# cheetah_driver_integrated_v2.net
KiCad netlist of a schematic drawn in EAGLE
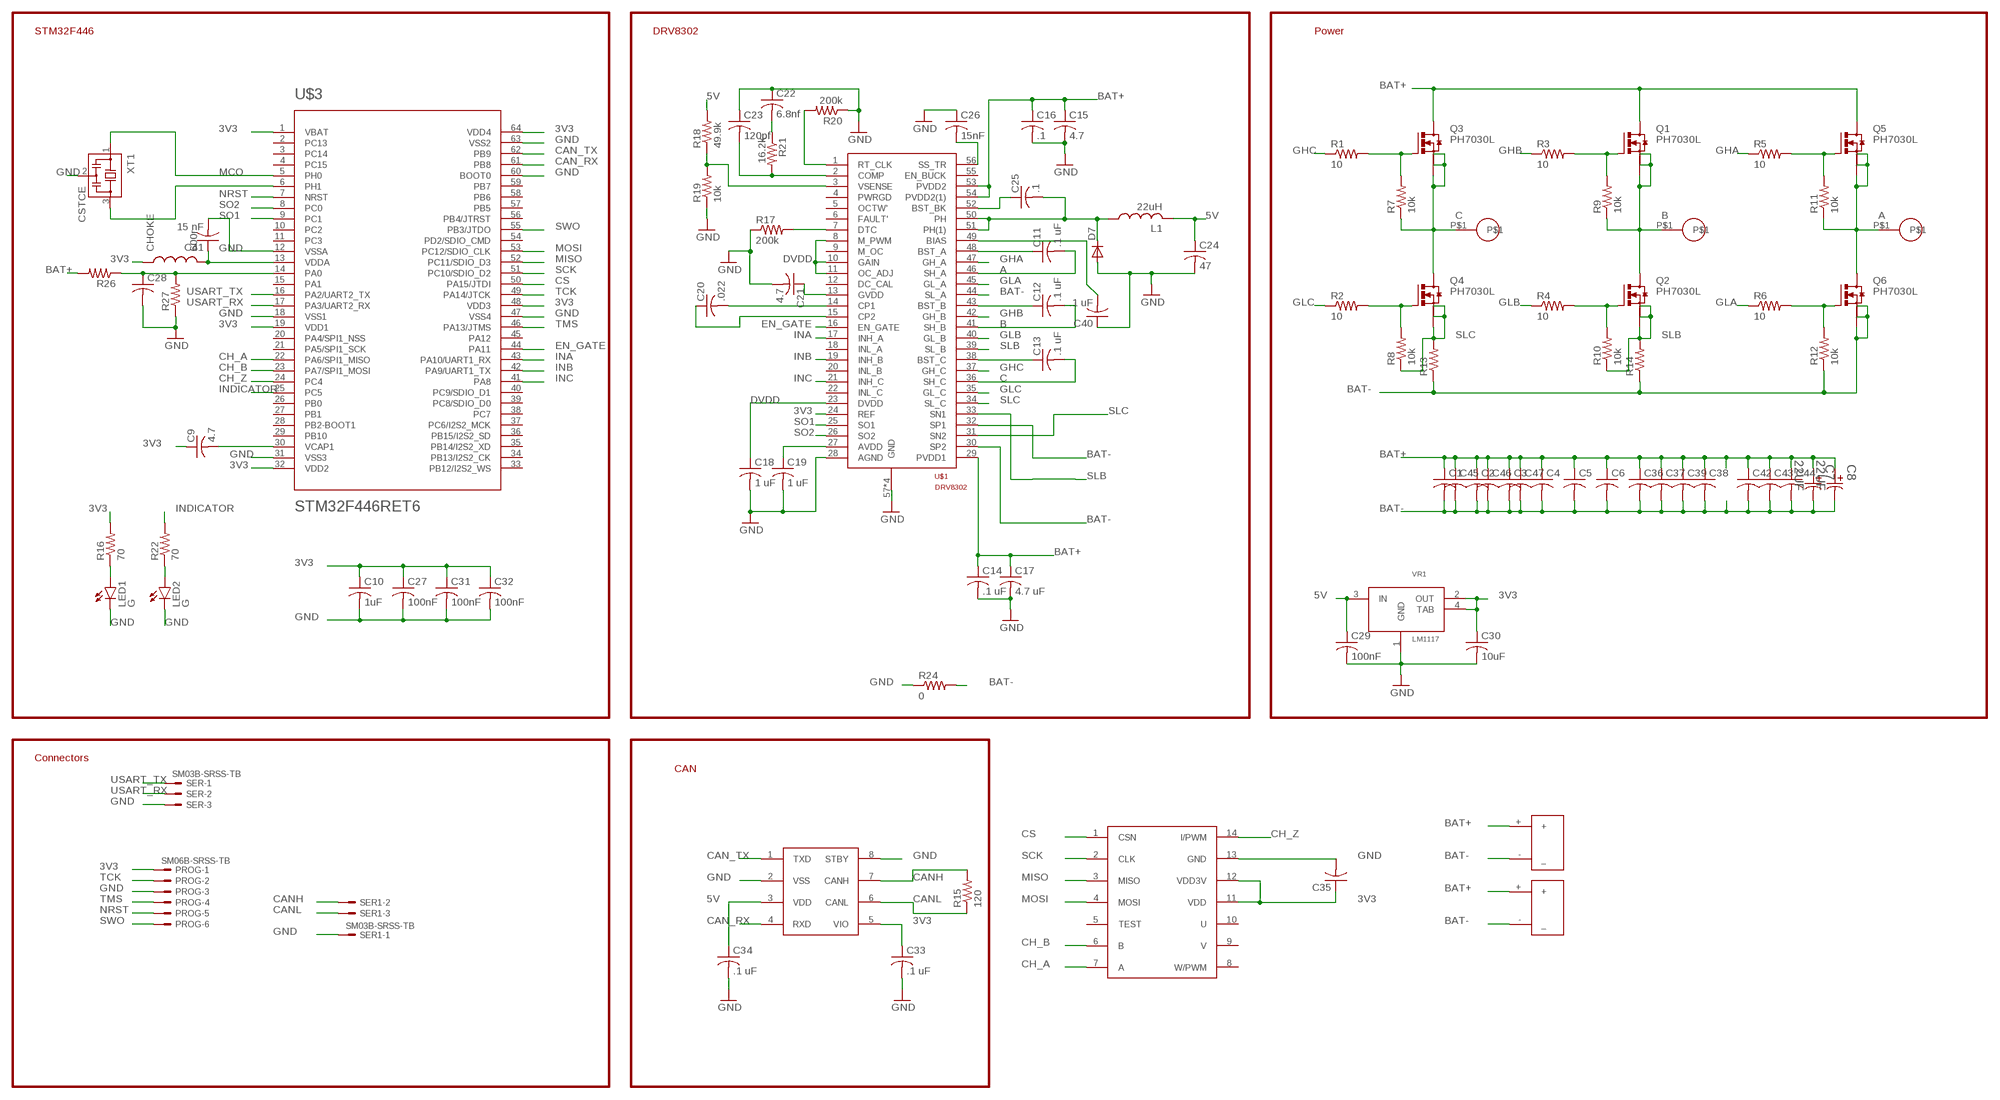
[diagram p0: schematic, sheet 1]

(export (version "E")
  (design (tool "Eeschema 10.0.6"))
  (components
    (comp (ref "C1")
      (value "C-USC1206")
      (footprint "eagle-import:C1206")
      (libsource (lib "eagle-import") (part "C-USC1206"))
    )
    (comp (ref "C2")
      (value "C-USC1206")
      (footprint "eagle-import:C1206")
      (libsource (lib "eagle-import") (part "C-USC1206"))
    )
    (comp (ref "C3")
      (value "C-USC1206")
      (footprint "eagle-import:C1206")
      (libsource (lib "eagle-import") (part "C-USC1206"))
    )
    (comp (ref "C4")
      (value "C-USC1206")
      (footprint "eagle-import:C1206")
      (libsource (lib "eagle-import") (part "C-USC1206"))
    )
    (comp (ref "C5")
      (value "C-USC1206")
      (footprint "eagle-import:C1206")
      (libsource (lib "eagle-import") (part "C-USC1206"))
    )
    (comp (ref "C6")
      (value "C-USC1206")
      (footprint "eagle-import:C1206")
      (libsource (lib "eagle-import") (part "C-USC1206"))
    )
    (comp (ref "C7")
      (value "22UF")
      (footprint "eagle-import:CAPAE660X610N")
      (fields (field (name "MPN") "EEE-HD1V220AP") (field (name "TOLERANCE") "±20 %"))
      (libsource (lib "eagle-import") (part "EEE--CASE-DHD1V220AP"))
    )
    (comp (ref "C8")
      (value "22UF")
      (footprint "eagle-import:CAPAE660X610N")
      (fields (field (name "MPN") "EEE-HD1V220AP") (field (name "TOLERANCE") "±20 %"))
      (libsource (lib "eagle-import") (part "EEE--CASE-DHD1V220AP"))
    )
    (comp (ref "C9")
      (value "4.7")
      (footprint "eagle-import:C0603")
      (libsource (lib "eagle-import") (part "C-USC0603"))
    )
    (comp (ref "C10")
      (value "1uF")
      (footprint "eagle-import:C0603")
      (libsource (lib "eagle-import") (part "C-USC0603"))
    )
    (comp (ref "C11")
      (value ".1 uF")
      (footprint "eagle-import:C0603")
      (libsource (lib "eagle-import") (part "C-USC0603"))
    )
    (comp (ref "C12")
      (value ".1 uF")
      (footprint "eagle-import:C0603")
      (libsource (lib "eagle-import") (part "C-USC0603"))
    )
    (comp (ref "C13")
      (value ".1 uF")
      (footprint "eagle-import:C0603")
      (libsource (lib "eagle-import") (part "C-USC0603"))
    )
    (comp (ref "C14")
      (value ".1 uF")
      (footprint "eagle-import:C0603")
      (libsource (lib "eagle-import") (part "C-USC0603"))
    )
    (comp (ref "C15")
      (value "4.7")
      (footprint "eagle-import:C0805")
      (libsource (lib "eagle-import") (part "C-USC0805"))
    )
    (comp (ref "C16")
      (value ".1")
      (footprint "eagle-import:C0603")
      (libsource (lib "eagle-import") (part "C-USC0603"))
    )
    (comp (ref "C17")
      (value "4.7 uF")
      (footprint "eagle-import:C0805")
      (libsource (lib "eagle-import") (part "C-USC0805"))
    )
    (comp (ref "C18")
      (value "1 uF")
      (footprint "eagle-import:C0603")
      (libsource (lib "eagle-import") (part "C-USC0603"))
    )
    (comp (ref "C19")
      (value "1 uF")
      (footprint "eagle-import:C0603")
      (libsource (lib "eagle-import") (part "C-USC0603"))
    )
    (comp (ref "C20")
      (value ".022")
      (footprint "eagle-import:C0603")
      (libsource (lib "eagle-import") (part "C-USC0603"))
    )
    (comp (ref "C21")
      (value "4.7")
      (footprint "eagle-import:C0805")
      (libsource (lib "eagle-import") (part "C-USC0805"))
    )
    (comp (ref "C22")
      (value "6.8nf")
      (footprint "eagle-import:C0603")
      (libsource (lib "eagle-import") (part "C-USC0603"))
    )
    (comp (ref "C23")
      (value "120pf")
      (footprint "eagle-import:C0603")
      (libsource (lib "eagle-import") (part "C-USC0603"))
    )
    (comp (ref "C24")
      (value "47")
      (footprint "eagle-import:C1210")
      (libsource (lib "eagle-import") (part "C-USC1210"))
    )
    (comp (ref "C25")
      (value ".1")
      (footprint "eagle-import:C0603")
      (libsource (lib "eagle-import") (part "C-USC0603"))
    )
    (comp (ref "C26")
      (value "15nF")
      (footprint "eagle-import:C0603")
      (libsource (lib "eagle-import") (part "C-USC0603"))
    )
    (comp (ref "C27")
      (value "100nF")
      (footprint "eagle-import:C0603")
      (libsource (lib "eagle-import") (part "C-USC0603"))
    )
    (comp (ref "C28")
      (value "C-USC0603")
      (footprint "eagle-import:C0603")
      (libsource (lib "eagle-import") (part "C-USC0603"))
    )
    (comp (ref "C29")
      (value "100nF")
      (footprint "eagle-import:C0603")
      (libsource (lib "eagle-import") (part "C-USC0603"))
    )
    (comp (ref "C30")
      (value "10uF")
      (footprint "eagle-import:C0805K")
      (libsource (lib "eagle-import") (part "C-USC0805K"))
    )
    (comp (ref "C31")
      (value "100nF")
      (footprint "eagle-import:C0603")
      (libsource (lib "eagle-import") (part "C-USC0603"))
    )
    (comp (ref "C32")
      (value "100nF")
      (footprint "eagle-import:C0603")
      (libsource (lib "eagle-import") (part "C-USC0603"))
    )
    (comp (ref "C33")
      (value ".1 uF")
      (footprint "eagle-import:C0603K")
      (libsource (lib "eagle-import") (part "C-USC0603K"))
    )
    (comp (ref "C34")
      (value ".1 uF")
      (footprint "eagle-import:C0603K")
      (libsource (lib "eagle-import") (part "C-USC0603K"))
    )
    (comp (ref "C35")
      (value "C-USC0603")
      (footprint "eagle-import:C0603")
      (libsource (lib "eagle-import") (part "C-USC0603"))
    )
    (comp (ref "C36")
      (value "C-USC1206")
      (footprint "eagle-import:C1206")
      (libsource (lib "eagle-import") (part "C-USC1206"))
    )
    (comp (ref "C37")
      (value "C-USC1206")
      (footprint "eagle-import:C1206")
      (libsource (lib "eagle-import") (part "C-USC1206"))
    )
    (comp (ref "C38")
      (value "C-USC1206")
      (footprint "eagle-import:C1206")
      (libsource (lib "eagle-import") (part "C-USC1206"))
    )
    (comp (ref "C39")
      (value "C-USC1206")
      (footprint "eagle-import:C1206")
      (libsource (lib "eagle-import") (part "C-USC1206"))
    )
    (comp (ref "C40")
      (value ".1 uF")
      (footprint "eagle-import:C0603")
      (libsource (lib "eagle-import") (part "C-USC0603"))
    )
    (comp (ref "C41")
      (value "15 nF")
      (footprint "eagle-import:C0603")
      (libsource (lib "eagle-import") (part "C-USC0603"))
    )
    (comp (ref "C42")
      (value "C-USC1206")
      (footprint "eagle-import:C1206")
      (libsource (lib "eagle-import") (part "C-USC1206"))
    )
    (comp (ref "C43")
      (value "C-USC1206")
      (footprint "eagle-import:C1206")
      (libsource (lib "eagle-import") (part "C-USC1206"))
    )
    (comp (ref "C44")
      (value "C-USC1206")
      (footprint "eagle-import:C1206")
      (libsource (lib "eagle-import") (part "C-USC1206"))
    )
    (comp (ref "C45")
      (value "C-USC1206")
      (footprint "eagle-import:C1206")
      (libsource (lib "eagle-import") (part "C-USC1206"))
    )
    (comp (ref "C46")
      (value "C-USC1206")
      (footprint "eagle-import:C1206")
      (libsource (lib "eagle-import") (part "C-USC1206"))
    )
    (comp (ref "C47")
      (value "C-USC1206")
      (footprint "eagle-import:C1206")
      (libsource (lib "eagle-import") (part "C-USC1206"))
    )
    (comp (ref "CHOKE")
      (value "600r")
      (footprint "eagle-import:0603")
      (libsource (lib "eagle-import") (part "INDUCTOR0603"))
    )
    (comp (ref "D7")
      (value "DIODE-DO-214AC")
      (footprint "eagle-import:DO-214AC")
      (libsource (lib "eagle-import") (part "DIODE-DO-214AC"))
    )
    (comp (ref "L1")
      (value "22uH")
      (footprint "eagle-import:L4532P")
      (libsource (lib "eagle-import") (part "L-USL4532P"))
    )
    (comp (ref "LED1")
      (value "G")
      (footprint "eagle-import:LED-0603")
      (libsource (lib "eagle-import") (part "LED0603"))
    )
    (comp (ref "LED2")
      (value "G")
      (footprint "eagle-import:LED-0603")
      (libsource (lib "eagle-import") (part "LED0603"))
    )
    (comp (ref "PROG")
      (value "SM06B-SRSS-TB")
      (footprint "eagle-import:SM06B-SRSS-TB")
      (libsource (lib "eagle-import") (part "?M06B-SRSS-TBS"))
    )
    (comp (ref "Q1")
      (value "PH7030L")
      (footprint "eagle-import:SOT669")
      (libsource (lib "eagle-import") (part "PH7030L"))
    )
    (comp (ref "Q2")
      (value "PH7030L")
      (footprint "eagle-import:SOT669")
      (libsource (lib "eagle-import") (part "PH7030L"))
    )
    (comp (ref "Q3")
      (value "PH7030L")
      (footprint "eagle-import:SOT669")
      (libsource (lib "eagle-import") (part "PH7030L"))
    )
    (comp (ref "Q4")
      (value "PH7030L")
      (footprint "eagle-import:SOT669")
      (libsource (lib "eagle-import") (part "PH7030L"))
    )
    (comp (ref "Q5")
      (value "PH7030L")
      (footprint "eagle-import:SOT669")
      (libsource (lib "eagle-import") (part "PH7030L"))
    )
    (comp (ref "Q6")
      (value "PH7030L")
      (footprint "eagle-import:SOT669")
      (libsource (lib "eagle-import") (part "PH7030L"))
    )
    (comp (ref "R1")
      (value "10")
      (footprint "eagle-import:R0603")
      (libsource (lib "eagle-import") (part "R-US_R0603"))
    )
    (comp (ref "R2")
      (value "10")
      (footprint "eagle-import:R0603")
      (libsource (lib "eagle-import") (part "R-US_R0603"))
    )
    (comp (ref "R3")
      (value "10")
      (footprint "eagle-import:R0603")
      (libsource (lib "eagle-import") (part "R-US_R0603"))
    )
    (comp (ref "R4")
      (value "10")
      (footprint "eagle-import:R0603")
      (libsource (lib "eagle-import") (part "R-US_R0603"))
    )
    (comp (ref "R5")
      (value "10")
      (footprint "eagle-import:R0603")
      (libsource (lib "eagle-import") (part "R-US_R0603"))
    )
    (comp (ref "R6")
      (value "10")
      (footprint "eagle-import:R0603")
      (libsource (lib "eagle-import") (part "R-US_R0603"))
    )
    (comp (ref "R7")
      (value "10k")
      (footprint "eagle-import:R0603")
      (libsource (lib "eagle-import") (part "R-US_R0603"))
    )
    (comp (ref "R8")
      (value "10k")
      (footprint "eagle-import:R0603")
      (libsource (lib "eagle-import") (part "R-US_R0603"))
    )
    (comp (ref "R9")
      (value "10k")
      (footprint "eagle-import:R0603")
      (libsource (lib "eagle-import") (part "R-US_R0603"))
    )
    (comp (ref "R10")
      (value "10k")
      (footprint "eagle-import:R0603")
      (libsource (lib "eagle-import") (part "R-US_R0603"))
    )
    (comp (ref "R11")
      (value "10k")
      (footprint "eagle-import:R0603")
      (libsource (lib "eagle-import") (part "R-US_R0603"))
    )
    (comp (ref "R12")
      (value "10k")
      (footprint "eagle-import:R0603")
      (libsource (lib "eagle-import") (part "R-US_R0603"))
    )
    (comp (ref "R13")
      (value "R-US_R1210")
      (footprint "eagle-import:R1210")
      (libsource (lib "eagle-import") (part "R-US_R1210"))
    )
    (comp (ref "R14")
      (value "R-US_R1210")
      (footprint "eagle-import:R1210")
      (libsource (lib "eagle-import") (part "R-US_R1210"))
    )
    (comp (ref "R15")
      (value "120")
      (footprint "eagle-import:R0603")
      (libsource (lib "eagle-import") (part "R-US_R0603"))
    )
    (comp (ref "R16")
      (value "70")
      (footprint "eagle-import:R0603")
      (libsource (lib "eagle-import") (part "R-US_R0603"))
    )
    (comp (ref "R17")
      (value "200k")
      (footprint "eagle-import:R0603")
      (libsource (lib "eagle-import") (part "R-US_R0603"))
    )
    (comp (ref "R18")
      (value "49.9k")
      (footprint "eagle-import:R0603")
      (libsource (lib "eagle-import") (part "R-US_R0603"))
    )
    (comp (ref "R19")
      (value "10k")
      (footprint "eagle-import:R0603")
      (libsource (lib "eagle-import") (part "R-US_R0603"))
    )
    (comp (ref "R20")
      (value "200k")
      (footprint "eagle-import:R0603")
      (libsource (lib "eagle-import") (part "R-US_R0603"))
    )
    (comp (ref "R21")
      (value "16.2k")
      (footprint "eagle-import:R0603")
      (libsource (lib "eagle-import") (part "R-US_R0603"))
    )
    (comp (ref "R22")
      (value "70")
      (footprint "eagle-import:R0603")
      (libsource (lib "eagle-import") (part "R-US_R0603"))
    )
    (comp (ref "R24")
      (value "0")
      (footprint "eagle-import:R0603")
      (libsource (lib "eagle-import") (part "R-US_R0603"))
    )
    (comp (ref "R26")
      (value "R-US_R0603")
      (footprint "eagle-import:R0603")
      (libsource (lib "eagle-import") (part "R-US_R0603"))
    )
    (comp (ref "R27")
      (value "R-US_R0603")
      (footprint "eagle-import:R0603")
      (libsource (lib "eagle-import") (part "R-US_R0603"))
    )
    (comp (ref "SER")
      (value "SM03B-SRSS-TB")
      (footprint "eagle-import:SM03B-SRSS-TB")
      (libsource (lib "eagle-import") (part "?M03B-SRSS-TBS"))
    )
    (comp (ref "SER1")
      (value "SM03B-SRSS-TB")
      (footprint "eagle-import:SM03B-SRSS-TB")
      (libsource (lib "eagle-import") (part "?M03B-SRSS-TBS"))
    )
    (comp (ref "U$1")
      (value "DRV8302")
      (footprint "eagle-import:HTSSOP56")
      (libsource (lib "eagle-import") (part "DRV8302"))
    )
    (comp (ref "U$2")
      (value "18_AWG_PAD")
      (footprint "eagle-import:18_AWG_PAD")
      (libsource (lib "eagle-import") (part "18_AWG_PAD"))
    )
    (comp (ref "U$3")
      (value "STM32F446RET6")
      (footprint "eagle-import:TQFP64")
      (libsource (lib "eagle-import") (part "STM32F446RET6"))
    )
    (comp (ref "U$4")
      (value "18_AWG_PAD")
      (footprint "eagle-import:18_AWG_PAD")
      (libsource (lib "eagle-import") (part "18_AWG_PAD"))
    )
    (comp (ref "U$5")
      (value "18_AWG_PAD")
      (footprint "eagle-import:18_AWG_PAD")
      (libsource (lib "eagle-import") (part "18_AWG_PAD"))
    )
    (comp (ref "U$6")
      (value "MCP2561")
      (footprint "eagle-import:SO08")
      (libsource (lib "eagle-import") (part "MCP2561"))
    )
    (comp (ref "U$7")
      (value "AS5147P")
      (footprint "eagle-import:TSSOP14")
      (libsource (lib "eagle-import") (part "AS5147P"))
    )
    (comp (ref "U$8")
      (value "DC_CONNECTOR")
      (footprint "eagle-import:XT30_HORIZONTAL")
      (libsource (lib "eagle-import") (part "DC_CONNECTOR"))
    )
    (comp (ref "U$9")
      (value "DC_CONNECTOR")
      (footprint "eagle-import:XT30_HORIZONTAL")
      (libsource (lib "eagle-import") (part "DC_CONNECTOR"))
    )
    (comp (ref "VR1")
      (value "LM1117")
      (footprint "eagle-import:SOT-223")
      (libsource (lib "eagle-import") (part "LM1117"))
    )
    (comp (ref "XT1")
      (value "CSTCE")
      (footprint "eagle-import:CSTCE")
      (libsource (lib "eagle-import") (part "CSTCE"))
    )
  )
  (nets
    (net (code "1") (name "/3V3") (class "Default")
      (node (ref "C10") (pin "1") (pinfunction "1_1") (pintype "passive"))
      (node (ref "C27") (pin "1") (pinfunction "1_1") (pintype "passive"))
      (node (ref "C30") (pin "1") (pinfunction "1_1") (pintype "passive"))
      (node (ref "C31") (pin "1") (pinfunction "1_1") (pintype "passive"))
      (node (ref "C32") (pin "1") (pinfunction "1_1") (pintype "passive"))
      (node (ref "C33") (pin "1") (pinfunction "1_1") (pintype "passive"))
      (node (ref "C35") (pin "1") (pinfunction "1_1") (pintype "passive"))
      (node (ref "C9") (pin "1") (pinfunction "1_1") (pintype "passive"))
      (node (ref "CHOKE") (pin "1") (pinfunction "1_1") (pintype "passive"))
      (node (ref "PROG") (pin "1") (pinfunction "S_1") (pintype "passive"))
      (node (ref "R16") (pin "2") (pinfunction "2_2") (pintype "passive"))
      (node (ref "U$1") (pin "24") (pinfunction "REF_24") (pintype "bidirectional"))
      (node (ref "U$3") (pin "1") (pinfunction "VBAT_1") (pintype "bidirectional"))
      (node (ref "U$3") (pin "19") (pinfunction "VDD1_19") (pintype "bidirectional"))
      (node (ref "U$3") (pin "32") (pinfunction "VDD2_32") (pintype "bidirectional"))
      (node (ref "U$3") (pin "48") (pinfunction "VDD3_48") (pintype "bidirectional"))
      (node (ref "U$3") (pin "64") (pinfunction "VDD4_64") (pintype "bidirectional"))
      (node (ref "U$6") (pin "5") (pinfunction "VIO_5") (pintype "bidirectional"))
      (node (ref "U$7") (pin "11") (pinfunction "VDD_11") (pintype "bidirectional"))
      (node (ref "U$7") (pin "12") (pinfunction "VDD3V_12") (pintype "bidirectional"))
      (node (ref "VR1") (pin "2") (pinfunction "OUT_2") (pintype "bidirectional"))
      (node (ref "VR1") (pin "4") (pinfunction "TAB_4") (pintype "bidirectional"))
    )
    (net (code "2") (name "/5V") (class "Default")
      (node (ref "C24") (pin "1") (pinfunction "1_1") (pintype "passive"))
      (node (ref "C29") (pin "1") (pinfunction "1_1") (pintype "passive"))
      (node (ref "C34") (pin "1") (pinfunction "1_1") (pintype "passive"))
      (node (ref "L1") (pin "2") (pinfunction "2_2") (pintype "passive"))
      (node (ref "R18") (pin "2") (pinfunction "2_2") (pintype "passive"))
      (node (ref "U$6") (pin "3") (pinfunction "VDD_3") (pintype "bidirectional"))
      (node (ref "VR1") (pin "3") (pinfunction "IN_3") (pintype "bidirectional"))
    )
    (net (code "3") (name "/A") (class "Default")
      (node (ref "C11") (pin "2") (pinfunction "2_2") (pintype "passive"))
      (node (ref "Q5") (pin "1") (pinfunction "S_1") (pintype "passive"))
      (node (ref "Q5") (pin "2") (pinfunction "S_2") (pintype "passive"))
      (node (ref "Q5") (pin "3") (pinfunction "S_3") (pintype "passive"))
      (node (ref "Q6") (pin "MB") (pinfunction "D_MB") (pintype "passive"))
      (node (ref "R11") (pin "1") (pinfunction "1_1") (pintype "passive"))
      (node (ref "U$1") (pin "46") (pinfunction "SH_A_46") (pintype "bidirectional"))
      (node (ref "U$5") (pin "P$1") (pinfunction "P$1_P$1") (pintype "bidirectional"))
    )
    (net (code "4") (name "/B") (class "Default")
      (node (ref "C12") (pin "2") (pinfunction "2_2") (pintype "passive"))
      (node (ref "Q1") (pin "1") (pinfunction "S_1") (pintype "passive"))
      (node (ref "Q1") (pin "2") (pinfunction "S_2") (pintype "passive"))
      (node (ref "Q1") (pin "3") (pinfunction "S_3") (pintype "passive"))
      (node (ref "Q2") (pin "MB") (pinfunction "D_MB") (pintype "passive"))
      (node (ref "R9") (pin "1") (pinfunction "1_1") (pintype "passive"))
      (node (ref "U$1") (pin "41") (pinfunction "SH_B_41") (pintype "bidirectional"))
      (node (ref "U$4") (pin "P$1") (pinfunction "P$1_P$1") (pintype "bidirectional"))
    )
    (net (code "5") (name "/BAT+") (class "Default")
      (node (ref "C1") (pin "1") (pinfunction "1_1") (pintype "passive"))
      (node (ref "C14") (pin "1") (pinfunction "1_1") (pintype "passive"))
      (node (ref "C15") (pin "1") (pinfunction "1_1") (pintype "passive"))
      (node (ref "C16") (pin "1") (pinfunction "1_1") (pintype "passive"))
      (node (ref "C17") (pin "1") (pinfunction "1_1") (pintype "passive"))
      (node (ref "C2") (pin "1") (pinfunction "1_1") (pintype "passive"))
      (node (ref "C3") (pin "1") (pinfunction "1_1") (pintype "passive"))
      (node (ref "C36") (pin "1") (pinfunction "1_1") (pintype "passive"))
      (node (ref "C37") (pin "1") (pinfunction "1_1") (pintype "passive"))
      (node (ref "C38") (pin "1") (pinfunction "1_1") (pintype "passive"))
      (node (ref "C39") (pin "1") (pinfunction "1_1") (pintype "passive"))
      (node (ref "C4") (pin "1") (pinfunction "1_1") (pintype "passive"))
      (node (ref "C42") (pin "1") (pinfunction "1_1") (pintype "passive"))
      (node (ref "C43") (pin "1") (pinfunction "1_1") (pintype "passive"))
      (node (ref "C44") (pin "1") (pinfunction "1_1") (pintype "passive"))
      (node (ref "C45") (pin "1") (pinfunction "1_1") (pintype "passive"))
      (node (ref "C46") (pin "1") (pinfunction "1_1") (pintype "passive"))
      (node (ref "C47") (pin "1") (pinfunction "1_1") (pintype "passive"))
      (node (ref "C5") (pin "1") (pinfunction "1_1") (pintype "passive"))
      (node (ref "C6") (pin "1") (pinfunction "1_1") (pintype "passive"))
      (node (ref "C7") (pin "1") (pinfunction "1_1") (pintype "passive"))
      (node (ref "C8") (pin "1") (pinfunction "1_1") (pintype "passive"))
      (node (ref "Q1") (pin "MB") (pinfunction "D_MB") (pintype "passive"))
      (node (ref "Q3") (pin "MB") (pinfunction "D_MB") (pintype "passive"))
      (node (ref "Q5") (pin "MB") (pinfunction "D_MB") (pintype "passive"))
      (node (ref "R26") (pin "2") (pinfunction "2_2") (pintype "passive"))
      (node (ref "U$1") (pin "29") (pinfunction "PVDD1_29") (pintype "bidirectional"))
      (node (ref "U$1") (pin "53") (pinfunction "PVDD2_53") (pintype "bidirectional"))
      (node (ref "U$1") (pin "54") (pinfunction "PVDD2(1)_54") (pintype "bidirectional"))
      (node (ref "U$8") (pin "+") (pinfunction "+_+") (pintype "bidirectional"))
      (node (ref "U$9") (pin "+") (pinfunction "+_+") (pintype "bidirectional"))
    )
    (net (code "6") (name "/BAT-") (class "Default")
      (node (ref "C1") (pin "2") (pinfunction "2_2") (pintype "passive"))
      (node (ref "C2") (pin "2") (pinfunction "2_2") (pintype "passive"))
      (node (ref "C3") (pin "2") (pinfunction "2_2") (pintype "passive"))
      (node (ref "C36") (pin "2") (pinfunction "2_2") (pintype "passive"))
      (node (ref "C37") (pin "2") (pinfunction "2_2") (pintype "passive"))
      (node (ref "C38") (pin "2") (pinfunction "2_2") (pintype "passive"))
      (node (ref "C39") (pin "2") (pinfunction "2_2") (pintype "passive"))
      (node (ref "C4") (pin "2") (pinfunction "2_2") (pintype "passive"))
      (node (ref "C42") (pin "2") (pinfunction "2_2") (pintype "passive"))
      (node (ref "C43") (pin "2") (pinfunction "2_2") (pintype "passive"))
      (node (ref "C44") (pin "2") (pinfunction "2_2") (pintype "passive"))
      (node (ref "C45") (pin "2") (pinfunction "2_2") (pintype "passive"))
      (node (ref "C46") (pin "2") (pinfunction "2_2") (pintype "passive"))
      (node (ref "C47") (pin "2") (pinfunction "2_2") (pintype "passive"))
      (node (ref "C5") (pin "2") (pinfunction "2_2") (pintype "passive"))
      (node (ref "C6") (pin "2") (pinfunction "2_2") (pintype "passive"))
      (node (ref "C7") (pin "2") (pinfunction "2_2") (pintype "passive"))
      (node (ref "C8") (pin "2") (pinfunction "2_2") (pintype "passive"))
      (node (ref "Q6") (pin "1") (pinfunction "S_1") (pintype "passive"))
      (node (ref "Q6") (pin "2") (pinfunction "S_2") (pintype "passive"))
      (node (ref "Q6") (pin "3") (pinfunction "S_3") (pintype "passive"))
      (node (ref "R12") (pin "1") (pinfunction "1_1") (pintype "passive"))
      (node (ref "R13") (pin "1") (pinfunction "1_1") (pintype "passive"))
      (node (ref "R14") (pin "1") (pinfunction "1_1") (pintype "passive"))
      (node (ref "R24") (pin "2") (pinfunction "2_2") (pintype "passive"))
      (node (ref "U$1") (pin "30") (pinfunction "SP2_30") (pintype "bidirectional"))
      (node (ref "U$1") (pin "32") (pinfunction "SP1_32") (pintype "bidirectional"))
      (node (ref "U$1") (pin "44") (pinfunction "SL_A_44") (pintype "bidirectional"))
      (node (ref "U$8") (pin "-") (pinfunction "__-") (pintype "bidirectional"))
      (node (ref "U$9") (pin "-") (pinfunction "__-") (pintype "bidirectional"))
    )
    (net (code "7") (name "/C") (class "Default")
      (node (ref "C13") (pin "2") (pinfunction "2_2") (pintype "passive"))
      (node (ref "Q3") (pin "1") (pinfunction "S_1") (pintype "passive"))
      (node (ref "Q3") (pin "2") (pinfunction "S_2") (pintype "passive"))
      (node (ref "Q3") (pin "3") (pinfunction "S_3") (pintype "passive"))
      (node (ref "Q4") (pin "MB") (pinfunction "D_MB") (pintype "passive"))
      (node (ref "R7") (pin "1") (pinfunction "1_1") (pintype "passive"))
      (node (ref "U$1") (pin "36") (pinfunction "SH_C_36") (pintype "bidirectional"))
      (node (ref "U$2") (pin "P$1") (pinfunction "P$1_P$1") (pintype "bidirectional"))
    )
    (net (code "8") (name "/CANH") (class "Default")
      (node (ref "R15") (pin "2") (pinfunction "2_2") (pintype "passive"))
      (node (ref "SER1") (pin "2") (pinfunction "S_2") (pintype "passive"))
      (node (ref "U$6") (pin "7") (pinfunction "CANH_7") (pintype "bidirectional"))
    )
    (net (code "9") (name "/CANL") (class "Default")
      (node (ref "R15") (pin "1") (pinfunction "1_1") (pintype "passive"))
      (node (ref "SER1") (pin "3") (pinfunction "S_3") (pintype "passive"))
      (node (ref "U$6") (pin "6") (pinfunction "CANL_6") (pintype "bidirectional"))
    )
    (net (code "10") (name "/CAN_RX") (class "Default")
      (node (ref "U$3") (pin "61") (pinfunction "PB8_61") (pintype "bidirectional"))
      (node (ref "U$6") (pin "4") (pinfunction "RXD_4") (pintype "bidirectional"))
    )
    (net (code "11") (name "/CAN_TX") (class "Default")
      (node (ref "U$3") (pin "62") (pinfunction "PB9_62") (pintype "bidirectional"))
      (node (ref "U$6") (pin "1") (pinfunction "TXD_1") (pintype "bidirectional"))
    )
    (net (code "12") (name "/CH_A") (class "Default")
      (node (ref "U$3") (pin "22") (pinfunction "PA6/SPI1_MISO_22") (pintype "bidirectional"))
      (node (ref "U$7") (pin "7") (pinfunction "A_7") (pintype "bidirectional"))
    )
    (net (code "13") (name "/CH_B") (class "Default")
      (node (ref "U$3") (pin "23") (pinfunction "PA7/SPI1_MOSI_23") (pintype "bidirectional"))
      (node (ref "U$7") (pin "6") (pinfunction "B_6") (pintype "bidirectional"))
    )
    (net (code "14") (name "/CH_Z") (class "Default")
      (node (ref "U$3") (pin "24") (pinfunction "PC4_24") (pintype "bidirectional"))
      (node (ref "U$7") (pin "14") (pinfunction "I/PWM_14") (pintype "bidirectional"))
    )
    (net (code "15") (name "/CS") (class "Default")
      (node (ref "U$3") (pin "50") (pinfunction "PA15/JTDI_50") (pintype "bidirectional"))
      (node (ref "U$7") (pin "1") (pinfunction "CSN_1") (pintype "bidirectional"))
    )
    (net (code "16") (name "/DVDD") (class "Default")
      (node (ref "C18") (pin "1") (pinfunction "1_1") (pintype "passive"))
      (node (ref "U$1") (pin "10") (pinfunction "GAIN_10") (pintype "bidirectional"))
      (node (ref "U$1") (pin "11") (pinfunction "OC_ADJ_11") (pintype "bidirectional"))
      (node (ref "U$1") (pin "23") (pinfunction "DVDD_23") (pintype "bidirectional"))
      (node (ref "U$1") (pin "8") (pinfunction "M_PWM_8") (pintype "bidirectional"))
    )
    (net (code "17") (name "/EN_GATE") (class "Default")
      (node (ref "U$1") (pin "16") (pinfunction "EN_GATE_16") (pintype "bidirectional"))
      (node (ref "U$3") (pin "44") (pinfunction "PA11_44") (pintype "bidirectional"))
    )
    (net (code "18") (name "/GHA") (class "Default")
      (node (ref "R5") (pin "1") (pinfunction "1_1") (pintype "passive"))
      (node (ref "U$1") (pin "47") (pinfunction "GH_A_47") (pintype "bidirectional"))
    )
    (net (code "19") (name "/GHB") (class "Default")
      (node (ref "R3") (pin "1") (pinfunction "1_1") (pintype "passive"))
      (node (ref "U$1") (pin "42") (pinfunction "GH_B_42") (pintype "bidirectional"))
    )
    (net (code "20") (name "/GHC") (class "Default")
      (node (ref "R1") (pin "1") (pinfunction "1_1") (pintype "passive"))
      (node (ref "U$1") (pin "37") (pinfunction "GH_C_37") (pintype "bidirectional"))
    )
    (net (code "21") (name "/GLA") (class "Default")
      (node (ref "R6") (pin "1") (pinfunction "1_1") (pintype "passive"))
      (node (ref "U$1") (pin "45") (pinfunction "GL_A_45") (pintype "bidirectional"))
    )
    (net (code "22") (name "/GLB") (class "Default")
      (node (ref "R4") (pin "1") (pinfunction "1_1") (pintype "passive"))
      (node (ref "U$1") (pin "40") (pinfunction "GL_B_40") (pintype "bidirectional"))
    )
    (net (code "23") (name "/GLC") (class "Default")
      (node (ref "R2") (pin "1") (pinfunction "1_1") (pintype "passive"))
      (node (ref "U$1") (pin "35") (pinfunction "GL_C_35") (pintype "bidirectional"))
    )
    (net (code "24") (name "/INA") (class "Default")
      (node (ref "U$1") (pin "17") (pinfunction "INH_A_17") (pintype "bidirectional"))
      (node (ref "U$3") (pin "43") (pinfunction "PA10/UART1_RX_43") (pintype "bidirectional"))
    )
    (net (code "25") (name "/INB") (class "Default")
      (node (ref "U$1") (pin "19") (pinfunction "INH_B_19") (pintype "bidirectional"))
      (node (ref "U$3") (pin "42") (pinfunction "PA9/UART1_TX_42") (pintype "bidirectional"))
    )
    (net (code "26") (name "/INC") (class "Default")
      (node (ref "U$1") (pin "21") (pinfunction "INH_C_21") (pintype "bidirectional"))
      (node (ref "U$3") (pin "41") (pinfunction "PA8_41") (pintype "bidirectional"))
    )
    (net (code "27") (name "/INDICATOR") (class "Default")
      (node (ref "R22") (pin "2") (pinfunction "2_2") (pintype "passive"))
      (node (ref "U$3") (pin "25") (pinfunction "PC5_25") (pintype "bidirectional"))
    )
    (net (code "28") (name "/MCO") (class "Default")
      (node (ref "U$3") (pin "5") (pinfunction "PH0_5") (pintype "bidirectional"))
      (node (ref "XT1") (pin "1") (pinfunction "1_1") (pintype "passive"))
    )
    (net (code "29") (name "/MISO") (class "Default")
      (node (ref "U$3") (pin "52") (pinfunction "PC11/SDIO_D3_52") (pintype "bidirectional"))
      (node (ref "U$7") (pin "3") (pinfunction "MISO_3") (pintype "bidirectional"))
    )
    (net (code "30") (name "/MOSI") (class "Default")
      (node (ref "U$3") (pin "53") (pinfunction "PC12/SDIO_CLK_53") (pintype "bidirectional"))
      (node (ref "U$7") (pin "4") (pinfunction "MOSI_4") (pintype "bidirectional"))
    )
    (net (code "31") (name "/NRST") (class "Default")
      (node (ref "PROG") (pin "5") (pinfunction "S_5") (pintype "passive"))
      (node (ref "U$3") (pin "7") (pinfunction "NRST_7") (pintype "bidirectional"))
    )
    (net (code "32") (name "/SCK") (class "Default")
      (node (ref "U$3") (pin "51") (pinfunction "PC10/SDIO_D2_51") (pintype "bidirectional"))
      (node (ref "U$7") (pin "2") (pinfunction "CLK_2") (pintype "bidirectional"))
    )
    (net (code "33") (name "/SLB") (class "Default")
      (node (ref "Q2") (pin "1") (pinfunction "S_1") (pintype "passive"))
      (node (ref "Q2") (pin "2") (pinfunction "S_2") (pintype "passive"))
      (node (ref "Q2") (pin "3") (pinfunction "S_3") (pintype "passive"))
      (node (ref "R10") (pin "1") (pinfunction "1_1") (pintype "passive"))
      (node (ref "R14") (pin "2") (pinfunction "2_2") (pintype "passive"))
      (node (ref "U$1") (pin "33") (pinfunction "SN1_33") (pintype "bidirectional"))
      (node (ref "U$1") (pin "39") (pinfunction "SL_B_39") (pintype "bidirectional"))
    )
    (net (code "34") (name "/SLC") (class "Default")
      (node (ref "Q4") (pin "1") (pinfunction "S_1") (pintype "passive"))
      (node (ref "Q4") (pin "2") (pinfunction "S_2") (pintype "passive"))
      (node (ref "Q4") (pin "3") (pinfunction "S_3") (pintype "passive"))
      (node (ref "R13") (pin "2") (pinfunction "2_2") (pintype "passive"))
      (node (ref "R8") (pin "1") (pinfunction "1_1") (pintype "passive"))
      (node (ref "U$1") (pin "31") (pinfunction "SN2_31") (pintype "bidirectional"))
      (node (ref "U$1") (pin "34") (pinfunction "SL_C_34") (pintype "bidirectional"))
    )
    (net (code "35") (name "/SO1") (class "Default")
      (node (ref "U$1") (pin "25") (pinfunction "SO1_25") (pintype "bidirectional"))
      (node (ref "U$3") (pin "9") (pinfunction "PC1_9") (pintype "bidirectional"))
    )
    (net (code "36") (name "/SO2") (class "Default")
      (node (ref "U$1") (pin "26") (pinfunction "SO2_26") (pintype "bidirectional"))
      (node (ref "U$3") (pin "8") (pinfunction "PC0_8") (pintype "bidirectional"))
    )
    (net (code "37") (name "/SWO") (class "Default")
      (node (ref "PROG") (pin "6") (pinfunction "S_6") (pintype "passive"))
      (node (ref "U$3") (pin "55") (pinfunction "PB3/JTDO_55") (pintype "bidirectional"))
    )
    (net (code "38") (name "/TCK") (class "Default")
      (node (ref "PROG") (pin "2") (pinfunction "S_2") (pintype "passive"))
      (node (ref "U$3") (pin "49") (pinfunction "PA14/JTCK_49") (pintype "bidirectional"))
    )
    (net (code "39") (name "/TMS") (class "Default")
      (node (ref "PROG") (pin "4") (pinfunction "S_4") (pintype "passive"))
      (node (ref "U$3") (pin "46") (pinfunction "PA13/JTMS_46") (pintype "bidirectional"))
    )
    (net (code "40") (name "/USART_RX") (class "Default")
      (node (ref "SER") (pin "2") (pinfunction "S_2") (pintype "passive"))
      (node (ref "U$3") (pin "17") (pinfunction "PA3/UART2_RX_17") (pintype "bidirectional"))
    )
    (net (code "41") (name "/USART_TX") (class "Default")
      (node (ref "SER") (pin "1") (pinfunction "S_1") (pintype "passive"))
      (node (ref "U$3") (pin "16") (pinfunction "PA2/UART2_TX_16") (pintype "bidirectional"))
    )
    (net (code "42") (name "GND") (class "Default")
      (node (ref "C10") (pin "2") (pinfunction "2_2") (pintype "passive"))
      (node (ref "C14") (pin "2") (pinfunction "2_2") (pintype "passive"))
      (node (ref "C15") (pin "2") (pinfunction "2_2") (pintype "passive"))
      (node (ref "C16") (pin "2") (pinfunction "2_2") (pintype "passive"))
      (node (ref "C17") (pin "2") (pinfunction "2_2") (pintype "passive"))
      (node (ref "C18") (pin "2") (pinfunction "2_2") (pintype "passive"))
      (node (ref "C19") (pin "2") (pinfunction "2_2") (pintype "passive"))
      (node (ref "C21") (pin "2") (pinfunction "2_2") (pintype "passive"))
      (node (ref "C22") (pin "1") (pinfunction "1_1") (pintype "passive"))
      (node (ref "C23") (pin "1") (pinfunction "1_1") (pintype "passive"))
      (node (ref "C24") (pin "2") (pinfunction "2_2") (pintype "passive"))
      (node (ref "C26") (pin "1") (pinfunction "1_1") (pintype "passive"))
      (node (ref "C27") (pin "2") (pinfunction "2_2") (pintype "passive"))
      (node (ref "C28") (pin "2") (pinfunction "2_2") (pintype "passive"))
      (node (ref "C29") (pin "2") (pinfunction "2_2") (pintype "passive"))
      (node (ref "C30") (pin "2") (pinfunction "2_2") (pintype "passive"))
      (node (ref "C31") (pin "2") (pinfunction "2_2") (pintype "passive"))
      (node (ref "C32") (pin "2") (pinfunction "2_2") (pintype "passive"))
      (node (ref "C33") (pin "2") (pinfunction "2_2") (pintype "passive"))
      (node (ref "C34") (pin "2") (pinfunction "2_2") (pintype "passive"))
      (node (ref "C35") (pin "2") (pinfunction "2_2") (pintype "passive"))
      (node (ref "C40") (pin "1") (pinfunction "1_1") (pintype "passive"))
      (node (ref "C41") (pin "2") (pinfunction "2_2") (pintype "passive"))
      (node (ref "D7") (pin "A") (pinfunction "A_A") (pintype "passive"))
      (node (ref "LED1") (pin "C") (pinfunction "C_C") (pintype "passive"))
      (node (ref "LED2") (pin "C") (pinfunction "C_C") (pintype "passive"))
      (node (ref "PROG") (pin "3") (pinfunction "S_3") (pintype "passive"))
      (node (ref "R17") (pin "1") (pinfunction "1_1") (pintype "passive"))
      (node (ref "R19") (pin "1") (pinfunction "1_1") (pintype "passive"))
      (node (ref "R20") (pin "1") (pinfunction "1_1") (pintype "passive"))
      (node (ref "R24") (pin "1") (pinfunction "1_1") (pintype "passive"))
      (node (ref "R27") (pin "1") (pinfunction "1_1") (pintype "passive"))
      (node (ref "SER") (pin "3") (pinfunction "S_3") (pintype "passive"))
      (node (ref "SER1") (pin "1") (pinfunction "S_1") (pintype "passive"))
      (node (ref "U$1") (pin "28") (pinfunction "AGND_28") (pintype "bidirectional"))
      (node (ref "U$1") (pin "57") (pinfunction "GND_57") (pintype "bidirectional"))
      (node (ref "U$1") (pin "P$1") (pinfunction "GND_P$1") (pintype "bidirectional"))
      (node (ref "U$1") (pin "P$2") (pinfunction "GND_P$2") (pintype "bidirectional"))
      (node (ref "U$1") (pin "P$3") (pinfunction "GND_P$3") (pintype "bidirectional"))
      (node (ref "U$3") (pin "12") (pinfunction "VSSA_12") (pintype "bidirectional"))
      (node (ref "U$3") (pin "18") (pinfunction "VSS1_18") (pintype "bidirectional"))
      (node (ref "U$3") (pin "31") (pinfunction "VSS3_31") (pintype "bidirectional"))
      (node (ref "U$3") (pin "47") (pinfunction "VSS4_47") (pintype "bidirectional"))
      (node (ref "U$3") (pin "60") (pinfunction "BOOT0_60") (pintype "bidirectional"))
      (node (ref "U$3") (pin "63") (pinfunction "VSS2_63") (pintype "bidirectional"))
      (node (ref "U$6") (pin "2") (pinfunction "VSS_2") (pintype "bidirectional"))
      (node (ref "U$6") (pin "8") (pinfunction "STBY_8") (pintype "bidirectional"))
      (node (ref "U$7") (pin "13") (pinfunction "GND_13") (pintype "bidirectional"))
      (node (ref "VR1") (pin "1") (pinfunction "GND_1") (pintype "bidirectional"))
      (node (ref "XT1") (pin "2") (pinfunction "2_2") (pintype "passive"))
    )
    (net (code "43") (name "Net-(C22-Pad2)") (class "Default")
      (node (ref "C22") (pin "2") (pinfunction "2_2") (pintype "passive"))
      (node (ref "R21") (pin "1") (pinfunction "1_1") (pintype "passive"))
    )
    (net (code "44") (name "Net-(LED1-PadA)") (class "Default")
      (node (ref "LED1") (pin "A") (pinfunction "A_A") (pintype "passive"))
      (node (ref "R16") (pin "1") (pinfunction "1_1") (pintype "passive"))
    )
    (net (code "45") (name "Net-(LED2-PadA)") (class "Default")
      (node (ref "LED2") (pin "A") (pinfunction "A_A") (pintype "passive"))
      (node (ref "R22") (pin "1") (pinfunction "1_1") (pintype "passive"))
    )
    (net (code "46") (name "Net-(Q1-G)") (class "Default")
      (node (ref "Q1") (pin "4") (pinfunction "G_4") (pintype "passive"))
      (node (ref "R3") (pin "2") (pinfunction "2_2") (pintype "passive"))
      (node (ref "R9") (pin "2") (pinfunction "2_2") (pintype "passive"))
    )
    (net (code "47") (name "Net-(Q2-G)") (class "Default")
      (node (ref "Q2") (pin "4") (pinfunction "G_4") (pintype "passive"))
      (node (ref "R10") (pin "2") (pinfunction "2_2") (pintype "passive"))
      (node (ref "R4") (pin "2") (pinfunction "2_2") (pintype "passive"))
    )
    (net (code "48") (name "Net-(Q3-G)") (class "Default")
      (node (ref "Q3") (pin "4") (pinfunction "G_4") (pintype "passive"))
      (node (ref "R1") (pin "2") (pinfunction "2_2") (pintype "passive"))
      (node (ref "R7") (pin "2") (pinfunction "2_2") (pintype "passive"))
    )
    (net (code "49") (name "Net-(Q4-G)") (class "Default")
      (node (ref "Q4") (pin "4") (pinfunction "G_4") (pintype "passive"))
      (node (ref "R2") (pin "2") (pinfunction "2_2") (pintype "passive"))
      (node (ref "R8") (pin "2") (pinfunction "2_2") (pintype "passive"))
    )
    (net (code "50") (name "Net-(Q5-G)") (class "Default")
      (node (ref "Q5") (pin "4") (pinfunction "G_4") (pintype "passive"))
      (node (ref "R11") (pin "2") (pinfunction "2_2") (pintype "passive"))
      (node (ref "R5") (pin "2") (pinfunction "2_2") (pintype "passive"))
    )
    (net (code "51") (name "Net-(Q6-G)") (class "Default")
      (node (ref "Q6") (pin "4") (pinfunction "G_4") (pintype "passive"))
      (node (ref "R12") (pin "2") (pinfunction "2_2") (pintype "passive"))
      (node (ref "R6") (pin "2") (pinfunction "2_2") (pintype "passive"))
    )
    (net (code "52") (name "Net-(U$1-AVDD)") (class "Default")
      (node (ref "C19") (pin "1") (pinfunction "1_1") (pintype "passive"))
      (node (ref "U$1") (pin "27") (pinfunction "AVDD_27") (pintype "bidirectional"))
    )
    (net (code "53") (name "Net-(U$1-BIAS)") (class "Default")
      (node (ref "C40") (pin "2") (pinfunction "2_2") (pintype "passive"))
      (node (ref "U$1") (pin "49") (pinfunction "BIAS_49") (pintype "bidirectional"))
    )
    (net (code "54") (name "Net-(U$1-BST_A)") (class "Default")
      (node (ref "C11") (pin "1") (pinfunction "1_1") (pintype "passive"))
      (node (ref "U$1") (pin "48") (pinfunction "BST_A_48") (pintype "bidirectional"))
    )
    (net (code "55") (name "Net-(U$1-BST_B)") (class "Default")
      (node (ref "C12") (pin "1") (pinfunction "1_1") (pintype "passive"))
      (node (ref "U$1") (pin "43") (pinfunction "BST_B_43") (pintype "bidirectional"))
    )
    (net (code "56") (name "Net-(U$1-BST_BK)") (class "Default")
      (node (ref "C25") (pin "1") (pinfunction "1_1") (pintype "passive"))
      (node (ref "U$1") (pin "52") (pinfunction "BST_BK_52") (pintype "bidirectional"))
    )
    (net (code "57") (name "Net-(U$1-BST_C)") (class "Default")
      (node (ref "C13") (pin "1") (pinfunction "1_1") (pintype "passive"))
      (node (ref "U$1") (pin "38") (pinfunction "BST_C_38") (pintype "bidirectional"))
    )
    (net (code "58") (name "Net-(U$1-COMP)") (class "Default")
      (node (ref "C23") (pin "2") (pinfunction "2_2") (pintype "passive"))
      (node (ref "R21") (pin "2") (pinfunction "2_2") (pintype "passive"))
      (node (ref "U$1") (pin "2") (pinfunction "COMP_2") (pintype "bidirectional"))
    )
    (net (code "59") (name "Net-(U$1-CP1)") (class "Default")
      (node (ref "C20") (pin "2") (pinfunction "2_2") (pintype "passive"))
      (node (ref "U$1") (pin "14") (pinfunction "CP1_14") (pintype "bidirectional"))
    )
    (net (code "60") (name "Net-(U$1-CP2)") (class "Default")
      (node (ref "C20") (pin "1") (pinfunction "1_1") (pintype "passive"))
      (node (ref "U$1") (pin "15") (pinfunction "CP2_15") (pintype "bidirectional"))
    )
    (net (code "61") (name "Net-(U$1-DTC)") (class "Default")
      (node (ref "R17") (pin "2") (pinfunction "2_2") (pintype "passive"))
      (node (ref "U$1") (pin "7") (pinfunction "DTC_7") (pintype "bidirectional"))
    )
    (net (code "62") (name "Net-(U$1-GVDD)") (class "Default")
      (node (ref "C21") (pin "1") (pinfunction "1_1") (pintype "passive"))
      (node (ref "U$1") (pin "13") (pinfunction "GVDD_13") (pintype "bidirectional"))
    )
    (net (code "63") (name "Net-(U$1-PH(1))") (class "Default")
      (node (ref "C25") (pin "2") (pinfunction "2_2") (pintype "passive"))
      (node (ref "D7") (pin "C") (pinfunction "C_C") (pintype "passive"))
      (node (ref "L1") (pin "1") (pinfunction "1_1") (pintype "passive"))
      (node (ref "U$1") (pin "50") (pinfunction "PH_50") (pintype "bidirectional"))
      (node (ref "U$1") (pin "51") (pinfunction "PH(1)_51") (pintype "bidirectional"))
    )
    (net (code "64") (name "Net-(U$1-RT_CLK)") (class "Default")
      (node (ref "R20") (pin "2") (pinfunction "2_2") (pintype "passive"))
      (node (ref "U$1") (pin "1") (pinfunction "RT_CLK_1") (pintype "bidirectional"))
    )
    (net (code "65") (name "Net-(U$1-SS_TR)") (class "Default")
      (node (ref "C26") (pin "2") (pinfunction "2_2") (pintype "passive"))
      (node (ref "U$1") (pin "56") (pinfunction "SS_TR_56") (pintype "bidirectional"))
    )
    (net (code "66") (name "Net-(U$1-VSENSE)") (class "Default")
      (node (ref "R18") (pin "1") (pinfunction "1_1") (pintype "passive"))
      (node (ref "R19") (pin "2") (pinfunction "2_2") (pintype "passive"))
      (node (ref "U$1") (pin "3") (pinfunction "VSENSE_3") (pintype "bidirectional"))
    )
    (net (code "67") (name "Net-(U$3-PA0)") (class "Default")
      (node (ref "C28") (pin "1") (pinfunction "1_1") (pintype "passive"))
      (node (ref "R26") (pin "1") (pinfunction "1_1") (pintype "passive"))
      (node (ref "R27") (pin "2") (pinfunction "2_2") (pintype "passive"))
      (node (ref "U$3") (pin "14") (pinfunction "PA0_14") (pintype "bidirectional"))
    )
    (net (code "68") (name "Net-(U$3-PH1)") (class "Default")
      (node (ref "U$3") (pin "6") (pinfunction "PH1_6") (pintype "bidirectional"))
      (node (ref "XT1") (pin "3") (pinfunction "3_3") (pintype "passive"))
    )
    (net (code "69") (name "Net-(U$3-VCAP1)") (class "Default")
      (node (ref "C9") (pin "2") (pinfunction "2_2") (pintype "passive"))
      (node (ref "U$3") (pin "30") (pinfunction "VCAP1_30") (pintype "bidirectional"))
    )
    (net (code "70") (name "Net-(U$3-VDDA)") (class "Default")
      (node (ref "C41") (pin "1") (pinfunction "1_1") (pintype "passive"))
      (node (ref "CHOKE") (pin "2") (pinfunction "2_2") (pintype "passive"))
      (node (ref "U$3") (pin "13") (pinfunction "VDDA_13") (pintype "bidirectional"))
    )
    (net (code "71") (name "unconnected-(U$1-DC_CAL-Pad12)") (class "Default")
      (node (ref "U$1") (pin "12") (pinfunction "DC_CAL_12") (pintype "bidirectional"))
    )
    (net (code "72") (name "unconnected-(U$1-EN_BUCK-Pad55)") (class "Default")
      (node (ref "U$1") (pin "55") (pinfunction "EN_BUCK_55") (pintype "bidirectional"))
    )
    (net (code "73") (name "unconnected-(U$1-FAULT'-Pad6)") (class "Default")
      (node (ref "U$1") (pin "6") (pinfunction "FAULT'_6") (pintype "bidirectional"))
    )
    (net (code "74") (name "unconnected-(U$1-INL_A-Pad18)") (class "Default")
      (node (ref "U$1") (pin "18") (pinfunction "INL_A_18") (pintype "bidirectional"))
    )
    (net (code "75") (name "unconnected-(U$1-INL_B-Pad20)") (class "Default")
      (node (ref "U$1") (pin "20") (pinfunction "INL_B_20") (pintype "bidirectional"))
    )
    (net (code "76") (name "unconnected-(U$1-INL_C-Pad22)") (class "Default")
      (node (ref "U$1") (pin "22") (pinfunction "INL_C_22") (pintype "bidirectional"))
    )
    (net (code "77") (name "unconnected-(U$1-M_OC-Pad9)") (class "Default")
      (node (ref "U$1") (pin "9") (pinfunction "M_OC_9") (pintype "bidirectional"))
    )
    (net (code "78") (name "unconnected-(U$1-OCTW'-Pad5)") (class "Default")
      (node (ref "U$1") (pin "5") (pinfunction "OCTW'_5") (pintype "bidirectional"))
    )
    (net (code "79") (name "unconnected-(U$1-PWRGD-Pad4)") (class "Default")
      (node (ref "U$1") (pin "4") (pinfunction "PWRGD_4") (pintype "bidirectional"))
    )
    (net (code "80") (name "unconnected-(U$3-PA1-Pad15)") (class "Default")
      (node (ref "U$3") (pin "15") (pinfunction "PA1_15") (pintype "bidirectional"))
    )
    (net (code "81") (name "unconnected-(U$3-PA4{slash}SPI1_NSS-Pad20)") (class "Default")
      (node (ref "U$3") (pin "20") (pinfunction "PA4/SPI1_NSS_20") (pintype "bidirectional"))
    )
    (net (code "82") (name "unconnected-(U$3-PA5{slash}SPI1_SCK-Pad21)") (class "Default")
      (node (ref "U$3") (pin "21") (pinfunction "PA5/SPI1_SCK_21") (pintype "bidirectional"))
    )
    (net (code "83") (name "unconnected-(U$3-PA12-Pad45)") (class "Default")
      (node (ref "U$3") (pin "45") (pinfunction "PA12_45") (pintype "bidirectional"))
    )
    (net (code "84") (name "unconnected-(U$3-PB0-Pad26)") (class "Default")
      (node (ref "U$3") (pin "26") (pinfunction "PB0_26") (pintype "bidirectional"))
    )
    (net (code "85") (name "unconnected-(U$3-PB1-Pad27)") (class "Default")
      (node (ref "U$3") (pin "27") (pinfunction "PB1_27") (pintype "bidirectional"))
    )
    (net (code "86") (name "unconnected-(U$3-PB2-BOOT1-Pad28)") (class "Default")
      (node (ref "U$3") (pin "28") (pinfunction "PB2-BOOT1_28") (pintype "bidirectional"))
    )
    (net (code "87") (name "unconnected-(U$3-PB4{slash}JTRST-Pad56)") (class "Default")
      (node (ref "U$3") (pin "56") (pinfunction "PB4/JTRST_56") (pintype "bidirectional"))
    )
    (net (code "88") (name "unconnected-(U$3-PB5-Pad57)") (class "Default")
      (node (ref "U$3") (pin "57") (pinfunction "PB5_57") (pintype "bidirectional"))
    )
    (net (code "89") (name "unconnected-(U$3-PB6-Pad58)") (class "Default")
      (node (ref "U$3") (pin "58") (pinfunction "PB6_58") (pintype "bidirectional"))
    )
    (net (code "90") (name "unconnected-(U$3-PB7-Pad59)") (class "Default")
      (node (ref "U$3") (pin "59") (pinfunction "PB7_59") (pintype "bidirectional"))
    )
    (net (code "91") (name "unconnected-(U$3-PB10-Pad29)") (class "Default")
      (node (ref "U$3") (pin "29") (pinfunction "PB10_29") (pintype "bidirectional"))
    )
    (net (code "92") (name "unconnected-(U$3-PB12{slash}I2S2_WS-Pad33)") (class "Default")
      (node (ref "U$3") (pin "33") (pinfunction "PB12/I2S2_WS_33") (pintype "bidirectional"))
    )
    (net (code "93") (name "unconnected-(U$3-PB13{slash}I2S2_CK-Pad34)") (class "Default")
      (node (ref "U$3") (pin "34") (pinfunction "PB13/I2S2_CK_34") (pintype "bidirectional"))
    )
    (net (code "94") (name "unconnected-(U$3-PB14{slash}I2S2_XD-Pad35)") (class "Default")
      (node (ref "U$3") (pin "35") (pinfunction "PB14/I2S2_XD_35") (pintype "bidirectional"))
    )
    (net (code "95") (name "unconnected-(U$3-PB15{slash}I2S2_SD-Pad36)") (class "Default")
      (node (ref "U$3") (pin "36") (pinfunction "PB15/I2S2_SD_36") (pintype "bidirectional"))
    )
    (net (code "96") (name "unconnected-(U$3-PC2-Pad10)") (class "Default")
      (node (ref "U$3") (pin "10") (pinfunction "PC2_10") (pintype "bidirectional"))
    )
    (net (code "97") (name "unconnected-(U$3-PC3-Pad11)") (class "Default")
      (node (ref "U$3") (pin "11") (pinfunction "PC3_11") (pintype "bidirectional"))
    )
    (net (code "98") (name "unconnected-(U$3-PC6{slash}I2S2_MCK-Pad37)") (class "Default")
      (node (ref "U$3") (pin "37") (pinfunction "PC6/I2S2_MCK_37") (pintype "bidirectional"))
    )
    (net (code "99") (name "unconnected-(U$3-PC7-Pad38)") (class "Default")
      (node (ref "U$3") (pin "38") (pinfunction "PC7_38") (pintype "bidirectional"))
    )
    (net (code "100") (name "unconnected-(U$3-PC8{slash}SDIO_D0-Pad39)") (class "Default")
      (node (ref "U$3") (pin "39") (pinfunction "PC8/SDIO_D0_39") (pintype "bidirectional"))
    )
    (net (code "101") (name "unconnected-(U$3-PC9{slash}SDIO_D1-Pad40)") (class "Default")
      (node (ref "U$3") (pin "40") (pinfunction "PC9/SDIO_D1_40") (pintype "bidirectional"))
    )
    (net (code "102") (name "unconnected-(U$3-PC13-Pad2)") (class "Default")
      (node (ref "U$3") (pin "2") (pinfunction "PC13_2") (pintype "bidirectional"))
    )
    (net (code "103") (name "unconnected-(U$3-PC14-Pad3)") (class "Default")
      (node (ref "U$3") (pin "3") (pinfunction "PC14_3") (pintype "bidirectional"))
    )
    (net (code "104") (name "unconnected-(U$3-PC15-Pad4)") (class "Default")
      (node (ref "U$3") (pin "4") (pinfunction "PC15_4") (pintype "bidirectional"))
    )
    (net (code "105") (name "unconnected-(U$3-PD2{slash}SDIO_CMD-Pad54)") (class "Default")
      (node (ref "U$3") (pin "54") (pinfunction "PD2/SDIO_CMD_54") (pintype "bidirectional"))
    )
    (net (code "106") (name "unconnected-(U$7-TEST-Pad5)") (class "Default")
      (node (ref "U$7") (pin "5") (pinfunction "TEST_5") (pintype "bidirectional"))
    )
    (net (code "107") (name "unconnected-(U$7-U-Pad10)") (class "Default")
      (node (ref "U$7") (pin "10") (pinfunction "U_10") (pintype "bidirectional"))
    )
    (net (code "108") (name "unconnected-(U$7-V-Pad9)") (class "Default")
      (node (ref "U$7") (pin "9") (pinfunction "V_9") (pintype "bidirectional"))
    )
    (net (code "109") (name "unconnected-(U$7-W{slash}PWM-Pad8)") (class "Default")
      (node (ref "U$7") (pin "8") (pinfunction "W/PWM_8") (pintype "bidirectional"))
    )
  )
)
